# Control_Board_4.net
KiCad netlist of a schematic drawn in EAGLE
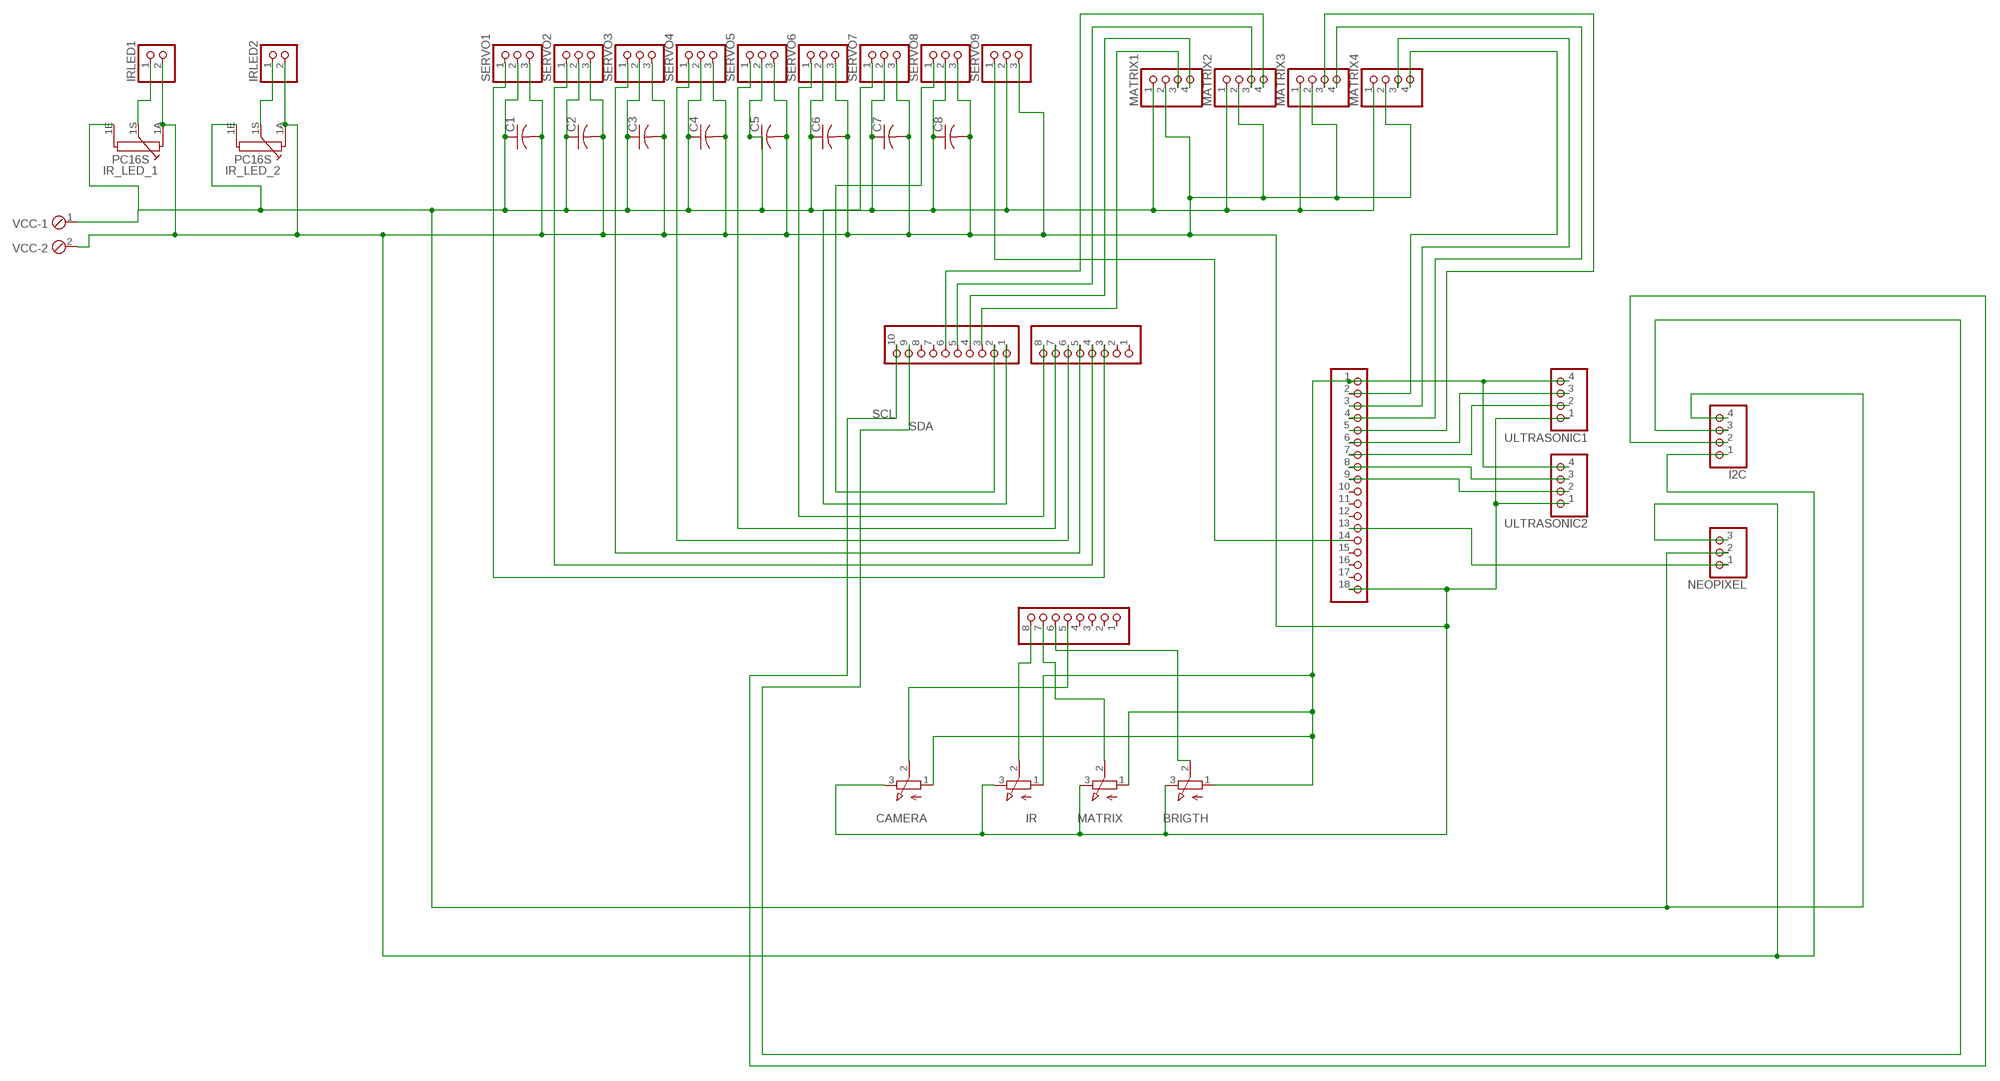
[diagram p0: schematic, sheet 1]

(export (version "E")
  (design (tool "Eeschema 10.0.6"))
  (components
    (comp (ref "BRIGTH")
      (value "3RP/1610N")
      (footprint "eagle-import:3RP_1610N")
      (libsource (lib "eagle-import") (part "3RP/1610N"))
    )
    (comp (ref "C1")
      (value "C-US050-030X075")
      (footprint "eagle-import:C050-030X075")
      (libsource (lib "eagle-import") (part "C-US050-030X075"))
    )
    (comp (ref "C2")
      (value "C-US050-030X075")
      (footprint "eagle-import:C050-030X075")
      (libsource (lib "eagle-import") (part "C-US050-030X075"))
    )
    (comp (ref "C3")
      (value "C-US050-030X075")
      (footprint "eagle-import:C050-030X075")
      (libsource (lib "eagle-import") (part "C-US050-030X075"))
    )
    (comp (ref "C4")
      (value "C-US050-030X075")
      (footprint "eagle-import:C050-030X075")
      (libsource (lib "eagle-import") (part "C-US050-030X075"))
    )
    (comp (ref "C5")
      (value "C-US050-030X075")
      (footprint "eagle-import:C050-030X075")
      (libsource (lib "eagle-import") (part "C-US050-030X075"))
    )
    (comp (ref "C6")
      (value "C-US050-030X075")
      (footprint "eagle-import:C050-030X075")
      (libsource (lib "eagle-import") (part "C-US050-030X075"))
    )
    (comp (ref "C7")
      (value "C-US050-030X075")
      (footprint "eagle-import:C050-030X075")
      (libsource (lib "eagle-import") (part "C-US050-030X075"))
    )
    (comp (ref "C8")
      (value "C-US050-030X075")
      (footprint "eagle-import:C050-030X075")
      (libsource (lib "eagle-import") (part "C-US050-030X075"))
    )
    (comp (ref "CAMERA")
      (value "3RP/1610N")
      (footprint "eagle-import:3RP_1610N")
      (libsource (lib "eagle-import") (part "3RP/1610N"))
    )
    (comp (ref "I2C")
      (value "PINHD-1X4")
      (footprint "eagle-import:1X04")
      (libsource (lib "eagle-import") (part "PINHD-1X4"))
    )
    (comp (ref "IR")
      (value "3RP/1610N")
      (footprint "eagle-import:3RP_1610N")
      (libsource (lib "eagle-import") (part "3RP/1610N"))
    )
    (comp (ref "IRLED1")
      (value "PINHD-1X2")
      (footprint "eagle-import:1X02")
      (libsource (lib "eagle-import") (part "PINHD-1X2"))
    )
    (comp (ref "IRLED2")
      (value "PINHD-1X2")
      (footprint "eagle-import:1X02")
      (libsource (lib "eagle-import") (part "PINHD-1X2"))
    )
    (comp (ref "IR_LED_1")
      (value "PC16S")
      (footprint "eagle-import:PC16S")
      (libsource (lib "eagle-import") (part "PC16S"))
    )
    (comp (ref "IR_LED_2")
      (value "PC16S")
      (footprint "eagle-import:PC16S")
      (libsource (lib "eagle-import") (part "PC16S"))
    )
    (comp (ref "MATRIX")
      (value "3RP/1610N")
      (footprint "eagle-import:3RP_1610N")
      (libsource (lib "eagle-import") (part "3RP/1610N"))
    )
    (comp (ref "MATRIX1")
      (value "PINHD-1X4")
      (footprint "eagle-import:1X04")
      (libsource (lib "eagle-import") (part "PINHD-1X4"))
    )
    (comp (ref "MATRIX2")
      (value "PINHD-1X4")
      (footprint "eagle-import:1X04")
      (libsource (lib "eagle-import") (part "PINHD-1X4"))
    )
    (comp (ref "MATRIX3")
      (value "PINHD-1X4")
      (footprint "eagle-import:1X04")
      (libsource (lib "eagle-import") (part "PINHD-1X4"))
    )
    (comp (ref "MATRIX4")
      (value "PINHD-1X4")
      (footprint "eagle-import:1X04")
      (libsource (lib "eagle-import") (part "PINHD-1X4"))
    )
    (comp (ref "MEGABOTTOMCENTER")
      (value "PINHD-1X8")
      (footprint "eagle-import:1X08")
      (libsource (lib "eagle-import") (part "PINHD-1X8"))
    )
    (comp (ref "MEGALATERAL")
      (value "PINHD-1X18")
      (footprint "eagle-import:1X18")
      (libsource (lib "eagle-import") (part "PINHD-1X18"))
    )
    (comp (ref "MEGATOPCENTER")
      (value "PINHD-1X8")
      (footprint "eagle-import:1X08")
      (libsource (lib "eagle-import") (part "PINHD-1X8"))
    )
    (comp (ref "MEGATOPLEFT")
      (value "PINHD-1X10_ARD")
      (footprint "eagle-import:1X10")
      (libsource (lib "eagle-import") (part "PINHD-1X10_ARD"))
    )
    (comp (ref "NEOPIXEL")
      (value "PINHD-1X3")
      (footprint "eagle-import:1X03")
      (libsource (lib "eagle-import") (part "PINHD-1X3"))
    )
    (comp (ref "SERVO1")
      (value "PINHD-1X3")
      (footprint "eagle-import:1X03")
      (libsource (lib "eagle-import") (part "PINHD-1X3"))
    )
    (comp (ref "SERVO2")
      (value "PINHD-1X3")
      (footprint "eagle-import:1X03")
      (libsource (lib "eagle-import") (part "PINHD-1X3"))
    )
    (comp (ref "SERVO3")
      (value "PINHD-1X3")
      (footprint "eagle-import:1X03")
      (libsource (lib "eagle-import") (part "PINHD-1X3"))
    )
    (comp (ref "SERVO4")
      (value "PINHD-1X3")
      (footprint "eagle-import:1X03")
      (libsource (lib "eagle-import") (part "PINHD-1X3"))
    )
    (comp (ref "SERVO5")
      (value "PINHD-1X3")
      (footprint "eagle-import:1X03")
      (libsource (lib "eagle-import") (part "PINHD-1X3"))
    )
    (comp (ref "SERVO6")
      (value "PINHD-1X3")
      (footprint "eagle-import:1X03")
      (libsource (lib "eagle-import") (part "PINHD-1X3"))
    )
    (comp (ref "SERVO7")
      (value "PINHD-1X3")
      (footprint "eagle-import:1X03")
      (libsource (lib "eagle-import") (part "PINHD-1X3"))
    )
    (comp (ref "SERVO8")
      (value "PINHD-1X3")
      (footprint "eagle-import:1X03")
      (libsource (lib "eagle-import") (part "PINHD-1X3"))
    )
    (comp (ref "SERVO9")
      (value "PINHD-1X3")
      (footprint "eagle-import:1X03")
      (libsource (lib "eagle-import") (part "PINHD-1X3"))
    )
    (comp (ref "ULTRASONIC1")
      (value "PINHD-1X4")
      (footprint "eagle-import:1X04")
      (libsource (lib "eagle-import") (part "PINHD-1X4"))
    )
    (comp (ref "ULTRASONIC2")
      (value "PINHD-1X4")
      (footprint "eagle-import:1X04")
      (libsource (lib "eagle-import") (part "PINHD-1X4"))
    )
    (comp (ref "VCC")
      (value "MPT2")
      (footprint "eagle-import:2POL254")
      (libsource (lib "eagle-import") (part "MPT2"))
    )
  )
  (nets
    (net (code "1") (name "/SCL") (class "Default")
      (node (ref "I2C") (pin "2") (pinfunction "2_2") (pintype "passive"))
      (node (ref "MEGATOPLEFT") (pin "10") (pinfunction "10_10") (pintype "passive"))
    )
    (net (code "2") (name "/SDA") (class "Default")
      (node (ref "I2C") (pin "3") (pinfunction "3_3") (pintype "passive"))
      (node (ref "MEGATOPLEFT") (pin "9") (pinfunction "9_9") (pintype "passive"))
    )
    (net (code "3") (name "Net-(BRIGTH-A)") (class "Default")
      (node (ref "BRIGTH") (pin "1") (pinfunction "A_1") (pintype "passive"))
      (node (ref "CAMERA") (pin "1") (pinfunction "A_1") (pintype "passive"))
      (node (ref "IR") (pin "1") (pinfunction "A_1") (pintype "passive"))
      (node (ref "MATRIX") (pin "1") (pinfunction "A_1") (pintype "passive"))
      (node (ref "MEGALATERAL") (pin "1") (pinfunction "1_1") (pintype "passive"))
      (node (ref "ULTRASONIC1") (pin "4") (pinfunction "4_4") (pintype "passive"))
      (node (ref "ULTRASONIC2") (pin "4") (pinfunction "4_4") (pintype "passive"))
    )
    (net (code "4") (name "Net-(BRIGTH-E)") (class "Default")
      (node (ref "BRIGTH") (pin "3") (pinfunction "E_3") (pintype "passive"))
      (node (ref "C1") (pin "2") (pinfunction "2_2") (pintype "passive"))
      (node (ref "C2") (pin "2") (pinfunction "2_2") (pintype "passive"))
      (node (ref "C3") (pin "2") (pinfunction "2_2") (pintype "passive"))
      (node (ref "C4") (pin "2") (pinfunction "2_2") (pintype "passive"))
      (node (ref "C5") (pin "2") (pinfunction "2_2") (pintype "passive"))
      (node (ref "C6") (pin "2") (pinfunction "2_2") (pintype "passive"))
      (node (ref "C7") (pin "2") (pinfunction "2_2") (pintype "passive"))
      (node (ref "C8") (pin "2") (pinfunction "2_2") (pintype "passive"))
      (node (ref "CAMERA") (pin "3") (pinfunction "E_3") (pintype "passive"))
      (node (ref "I2C") (pin "1") (pinfunction "1_1") (pintype "passive"))
      (node (ref "IR") (pin "3") (pinfunction "E_3") (pintype "passive"))
      (node (ref "IRLED1") (pin "2") (pinfunction "2_2") (pintype "passive"))
      (node (ref "IRLED2") (pin "2") (pinfunction "2_2") (pintype "passive"))
      (node (ref "IR_LED_1") (pin "1A") (pinfunction "1A_1A") (pintype "passive"))
      (node (ref "IR_LED_2") (pin "1A") (pinfunction "1A_1A") (pintype "passive"))
      (node (ref "MATRIX") (pin "3") (pinfunction "E_3") (pintype "passive"))
      (node (ref "MATRIX1") (pin "2") (pinfunction "2_2") (pintype "passive"))
      (node (ref "MATRIX2") (pin "2") (pinfunction "2_2") (pintype "passive"))
      (node (ref "MATRIX3") (pin "2") (pinfunction "2_2") (pintype "passive"))
      (node (ref "MATRIX4") (pin "2") (pinfunction "2_2") (pintype "passive"))
      (node (ref "MEGALATERAL") (pin "18") (pinfunction "18_18") (pintype "passive"))
      (node (ref "NEOPIXEL") (pin "3") (pinfunction "3_3") (pintype "passive"))
      (node (ref "SERVO1") (pin "3") (pinfunction "3_3") (pintype "passive"))
      (node (ref "SERVO2") (pin "3") (pinfunction "3_3") (pintype "passive"))
      (node (ref "SERVO3") (pin "3") (pinfunction "3_3") (pintype "passive"))
      (node (ref "SERVO4") (pin "3") (pinfunction "3_3") (pintype "passive"))
      (node (ref "SERVO5") (pin "3") (pinfunction "3_3") (pintype "passive"))
      (node (ref "SERVO6") (pin "3") (pinfunction "3_3") (pintype "passive"))
      (node (ref "SERVO7") (pin "3") (pinfunction "3_3") (pintype "passive"))
      (node (ref "SERVO8") (pin "3") (pinfunction "3_3") (pintype "passive"))
      (node (ref "SERVO9") (pin "3") (pinfunction "3_3") (pintype "passive"))
      (node (ref "ULTRASONIC1") (pin "1") (pinfunction "1_1") (pintype "passive"))
      (node (ref "ULTRASONIC2") (pin "1") (pinfunction "1_1") (pintype "passive"))
      (node (ref "VCC") (pin "2") (pinfunction "1_2") (pintype "passive"))
    )
    (net (code "5") (name "Net-(BRIGTH-S)") (class "Default")
      (node (ref "BRIGTH") (pin "2") (pinfunction "S_2") (pintype "passive"))
      (node (ref "MEGABOTTOMCENTER") (pin "6") (pinfunction "6_6") (pintype "passive"))
    )
    (net (code "6") (name "Net-(C1-Pad1)") (class "Default")
      (node (ref "C1") (pin "1") (pinfunction "1_1") (pintype "passive"))
      (node (ref "C2") (pin "1") (pinfunction "1_1") (pintype "passive"))
      (node (ref "C3") (pin "1") (pinfunction "1_1") (pintype "passive"))
      (node (ref "C4") (pin "1") (pinfunction "1_1") (pintype "passive"))
      (node (ref "C5") (pin "1") (pinfunction "1_1") (pintype "passive"))
      (node (ref "C6") (pin "1") (pinfunction "1_1") (pintype "passive"))
      (node (ref "C7") (pin "1") (pinfunction "1_1") (pintype "passive"))
      (node (ref "C8") (pin "1") (pinfunction "1_1") (pintype "passive"))
      (node (ref "I2C") (pin "4") (pinfunction "4_4") (pintype "passive"))
      (node (ref "IR_LED_1") (pin "1E") (pinfunction "1E_1E") (pintype "passive"))
      (node (ref "IR_LED_2") (pin "1E") (pinfunction "1E_1E") (pintype "passive"))
      (node (ref "MATRIX1") (pin "1") (pinfunction "1_1") (pintype "passive"))
      (node (ref "MATRIX2") (pin "1") (pinfunction "1_1") (pintype "passive"))
      (node (ref "MATRIX3") (pin "1") (pinfunction "1_1") (pintype "passive"))
      (node (ref "MATRIX4") (pin "1") (pinfunction "1_1") (pintype "passive"))
      (node (ref "NEOPIXEL") (pin "2") (pinfunction "2_2") (pintype "passive"))
      (node (ref "SERVO1") (pin "2") (pinfunction "2_2") (pintype "passive"))
      (node (ref "SERVO2") (pin "2") (pinfunction "2_2") (pintype "passive"))
      (node (ref "SERVO3") (pin "2") (pinfunction "2_2") (pintype "passive"))
      (node (ref "SERVO4") (pin "2") (pinfunction "2_2") (pintype "passive"))
      (node (ref "SERVO5") (pin "2") (pinfunction "2_2") (pintype "passive"))
      (node (ref "SERVO6") (pin "2") (pinfunction "2_2") (pintype "passive"))
      (node (ref "SERVO7") (pin "2") (pinfunction "2_2") (pintype "passive"))
      (node (ref "SERVO8") (pin "2") (pinfunction "2_2") (pintype "passive"))
      (node (ref "SERVO9") (pin "2") (pinfunction "2_2") (pintype "passive"))
      (node (ref "VCC") (pin "1") (pinfunction "1_1") (pintype "passive"))
    )
    (net (code "7") (name "Net-(CAMERA-S)") (class "Default")
      (node (ref "CAMERA") (pin "2") (pinfunction "S_2") (pintype "passive"))
      (node (ref "MEGABOTTOMCENTER") (pin "5") (pinfunction "5_5") (pintype "passive"))
    )
    (net (code "8") (name "Net-(IR-S)") (class "Default")
      (node (ref "IR") (pin "2") (pinfunction "S_2") (pintype "passive"))
      (node (ref "MEGABOTTOMCENTER") (pin "8") (pinfunction "8_8") (pintype "passive"))
    )
    (net (code "9") (name "Net-(IRLED1-Pad1)") (class "Default")
      (node (ref "IRLED1") (pin "1") (pinfunction "1_1") (pintype "passive"))
      (node (ref "IR_LED_1") (pin "1S") (pinfunction "1S_1S") (pintype "passive"))
    )
    (net (code "10") (name "Net-(IRLED2-Pad1)") (class "Default")
      (node (ref "IRLED2") (pin "1") (pinfunction "1_1") (pintype "passive"))
      (node (ref "IR_LED_2") (pin "1S") (pinfunction "1S_1S") (pintype "passive"))
    )
    (net (code "11") (name "Net-(MATRIX-S)") (class "Default")
      (node (ref "MATRIX") (pin "2") (pinfunction "S_2") (pintype "passive"))
      (node (ref "MEGABOTTOMCENTER") (pin "7") (pinfunction "7_7") (pintype "passive"))
    )
    (net (code "12") (name "Net-(MATRIX1-Pad3)") (class "Default")
      (node (ref "MATRIX1") (pin "3") (pinfunction "3_3") (pintype "passive"))
      (node (ref "MEGATOPLEFT") (pin "3") (pinfunction "3_3") (pintype "passive"))
    )
    (net (code "13") (name "Net-(MATRIX1-Pad4)") (class "Default")
      (node (ref "MATRIX1") (pin "4") (pinfunction "4_4") (pintype "passive"))
      (node (ref "MEGATOPLEFT") (pin "4") (pinfunction "4_4") (pintype "passive"))
    )
    (net (code "14") (name "Net-(MATRIX2-Pad3)") (class "Default")
      (node (ref "MATRIX2") (pin "3") (pinfunction "3_3") (pintype "passive"))
      (node (ref "MEGATOPLEFT") (pin "5") (pinfunction "5_5") (pintype "passive"))
    )
    (net (code "15") (name "Net-(MATRIX2-Pad4)") (class "Default")
      (node (ref "MATRIX2") (pin "4") (pinfunction "4_4") (pintype "passive"))
      (node (ref "MEGATOPLEFT") (pin "6") (pinfunction "6_6") (pintype "passive"))
    )
    (net (code "16") (name "Net-(MATRIX3-Pad3)") (class "Default")
      (node (ref "MATRIX3") (pin "3") (pinfunction "3_3") (pintype "passive"))
      (node (ref "MEGALATERAL") (pin "5") (pinfunction "5_5") (pintype "passive"))
    )
    (net (code "17") (name "Net-(MATRIX3-Pad4)") (class "Default")
      (node (ref "MATRIX3") (pin "4") (pinfunction "4_4") (pintype "passive"))
      (node (ref "MEGALATERAL") (pin "4") (pinfunction "4_4") (pintype "passive"))
    )
    (net (code "18") (name "Net-(MATRIX4-Pad3)") (class "Default")
      (node (ref "MATRIX4") (pin "3") (pinfunction "3_3") (pintype "passive"))
      (node (ref "MEGALATERAL") (pin "3") (pinfunction "3_3") (pintype "passive"))
    )
    (net (code "19") (name "Net-(MATRIX4-Pad4)") (class "Default")
      (node (ref "MATRIX4") (pin "4") (pinfunction "4_4") (pintype "passive"))
      (node (ref "MEGALATERAL") (pin "2") (pinfunction "2_2") (pintype "passive"))
    )
    (net (code "20") (name "Net-(MEGALATERAL-Pad6)") (class "Default")
      (node (ref "MEGALATERAL") (pin "6") (pinfunction "6_6") (pintype "passive"))
      (node (ref "ULTRASONIC1") (pin "3") (pinfunction "3_3") (pintype "passive"))
    )
    (net (code "21") (name "Net-(MEGALATERAL-Pad7)") (class "Default")
      (node (ref "MEGALATERAL") (pin "7") (pinfunction "7_7") (pintype "passive"))
      (node (ref "ULTRASONIC1") (pin "2") (pinfunction "2_2") (pintype "passive"))
    )
    (net (code "22") (name "Net-(MEGALATERAL-Pad8)") (class "Default")
      (node (ref "MEGALATERAL") (pin "8") (pinfunction "8_8") (pintype "passive"))
      (node (ref "ULTRASONIC2") (pin "3") (pinfunction "3_3") (pintype "passive"))
    )
    (net (code "23") (name "Net-(MEGALATERAL-Pad9)") (class "Default")
      (node (ref "MEGALATERAL") (pin "9") (pinfunction "9_9") (pintype "passive"))
      (node (ref "ULTRASONIC2") (pin "2") (pinfunction "2_2") (pintype "passive"))
    )
    (net (code "24") (name "Net-(MEGALATERAL-Pad13)") (class "Default")
      (node (ref "MEGALATERAL") (pin "13") (pinfunction "13_13") (pintype "passive"))
      (node (ref "NEOPIXEL") (pin "1") (pinfunction "1_1") (pintype "passive"))
    )
    (net (code "25") (name "Net-(MEGALATERAL-Pad14)") (class "Default")
      (node (ref "MEGALATERAL") (pin "14") (pinfunction "14_14") (pintype "passive"))
      (node (ref "SERVO9") (pin "1") (pinfunction "1_1") (pintype "passive"))
    )
    (net (code "26") (name "Net-(MEGATOPCENTER-Pad3)") (class "Default")
      (node (ref "MEGATOPCENTER") (pin "3") (pinfunction "3_3") (pintype "passive"))
      (node (ref "SERVO1") (pin "1") (pinfunction "1_1") (pintype "passive"))
    )
    (net (code "27") (name "Net-(MEGATOPCENTER-Pad4)") (class "Default")
      (node (ref "MEGATOPCENTER") (pin "4") (pinfunction "4_4") (pintype "passive"))
      (node (ref "SERVO2") (pin "1") (pinfunction "1_1") (pintype "passive"))
    )
    (net (code "28") (name "Net-(MEGATOPCENTER-Pad5)") (class "Default")
      (node (ref "MEGATOPCENTER") (pin "5") (pinfunction "5_5") (pintype "passive"))
      (node (ref "SERVO3") (pin "1") (pinfunction "1_1") (pintype "passive"))
    )
    (net (code "29") (name "Net-(MEGATOPCENTER-Pad6)") (class "Default")
      (node (ref "MEGATOPCENTER") (pin "6") (pinfunction "6_6") (pintype "passive"))
      (node (ref "SERVO4") (pin "1") (pinfunction "1_1") (pintype "passive"))
    )
    (net (code "30") (name "Net-(MEGATOPCENTER-Pad7)") (class "Default")
      (node (ref "MEGATOPCENTER") (pin "7") (pinfunction "7_7") (pintype "passive"))
      (node (ref "SERVO5") (pin "1") (pinfunction "1_1") (pintype "passive"))
    )
    (net (code "31") (name "Net-(MEGATOPCENTER-Pad8)") (class "Default")
      (node (ref "MEGATOPCENTER") (pin "8") (pinfunction "8_8") (pintype "passive"))
      (node (ref "SERVO6") (pin "1") (pinfunction "1_1") (pintype "passive"))
    )
    (net (code "32") (name "Net-(MEGATOPLEFT-Pad1)") (class "Default")
      (node (ref "MEGATOPLEFT") (pin "1") (pinfunction "1_1") (pintype "passive"))
      (node (ref "SERVO7") (pin "1") (pinfunction "1_1") (pintype "passive"))
    )
    (net (code "33") (name "Net-(MEGATOPLEFT-Pad2)") (class "Default")
      (node (ref "MEGATOPLEFT") (pin "2") (pinfunction "2_2") (pintype "passive"))
      (node (ref "SERVO8") (pin "1") (pinfunction "1_1") (pintype "passive"))
    )
    (net (code "34") (name "unconnected-(MEGABOTTOMCENTER-Pad1)") (class "Default")
      (node (ref "MEGABOTTOMCENTER") (pin "1") (pinfunction "1_1") (pintype "passive"))
    )
    (net (code "35") (name "unconnected-(MEGABOTTOMCENTER-Pad2)") (class "Default")
      (node (ref "MEGABOTTOMCENTER") (pin "2") (pinfunction "2_2") (pintype "passive"))
    )
    (net (code "36") (name "unconnected-(MEGABOTTOMCENTER-Pad3)") (class "Default")
      (node (ref "MEGABOTTOMCENTER") (pin "3") (pinfunction "3_3") (pintype "passive"))
    )
    (net (code "37") (name "unconnected-(MEGABOTTOMCENTER-Pad4)") (class "Default")
      (node (ref "MEGABOTTOMCENTER") (pin "4") (pinfunction "4_4") (pintype "passive"))
    )
    (net (code "38") (name "unconnected-(MEGALATERAL-Pad10)") (class "Default")
      (node (ref "MEGALATERAL") (pin "10") (pinfunction "10_10") (pintype "passive"))
    )
    (net (code "39") (name "unconnected-(MEGALATERAL-Pad11)") (class "Default")
      (node (ref "MEGALATERAL") (pin "11") (pinfunction "11_11") (pintype "passive"))
    )
    (net (code "40") (name "unconnected-(MEGALATERAL-Pad12)") (class "Default")
      (node (ref "MEGALATERAL") (pin "12") (pinfunction "12_12") (pintype "passive"))
    )
    (net (code "41") (name "unconnected-(MEGALATERAL-Pad15)") (class "Default")
      (node (ref "MEGALATERAL") (pin "15") (pinfunction "15_15") (pintype "passive"))
    )
    (net (code "42") (name "unconnected-(MEGALATERAL-Pad16)") (class "Default")
      (node (ref "MEGALATERAL") (pin "16") (pinfunction "16_16") (pintype "passive"))
    )
    (net (code "43") (name "unconnected-(MEGALATERAL-Pad17)") (class "Default")
      (node (ref "MEGALATERAL") (pin "17") (pinfunction "17_17") (pintype "passive"))
    )
    (net (code "44") (name "unconnected-(MEGATOPCENTER-Pad1)") (class "Default")
      (node (ref "MEGATOPCENTER") (pin "1") (pinfunction "1_1") (pintype "passive"))
    )
    (net (code "45") (name "unconnected-(MEGATOPCENTER-Pad2)") (class "Default")
      (node (ref "MEGATOPCENTER") (pin "2") (pinfunction "2_2") (pintype "passive"))
    )
    (net (code "46") (name "unconnected-(MEGATOPLEFT-Pad7)") (class "Default")
      (node (ref "MEGATOPLEFT") (pin "7") (pinfunction "7_7") (pintype "passive"))
    )
    (net (code "47") (name "unconnected-(MEGATOPLEFT-Pad8)") (class "Default")
      (node (ref "MEGATOPLEFT") (pin "8") (pinfunction "8_8") (pintype "passive"))
    )
  )
)
